# LLAP_Temp.net
KiCad netlist of a schematic drawn in EAGLE
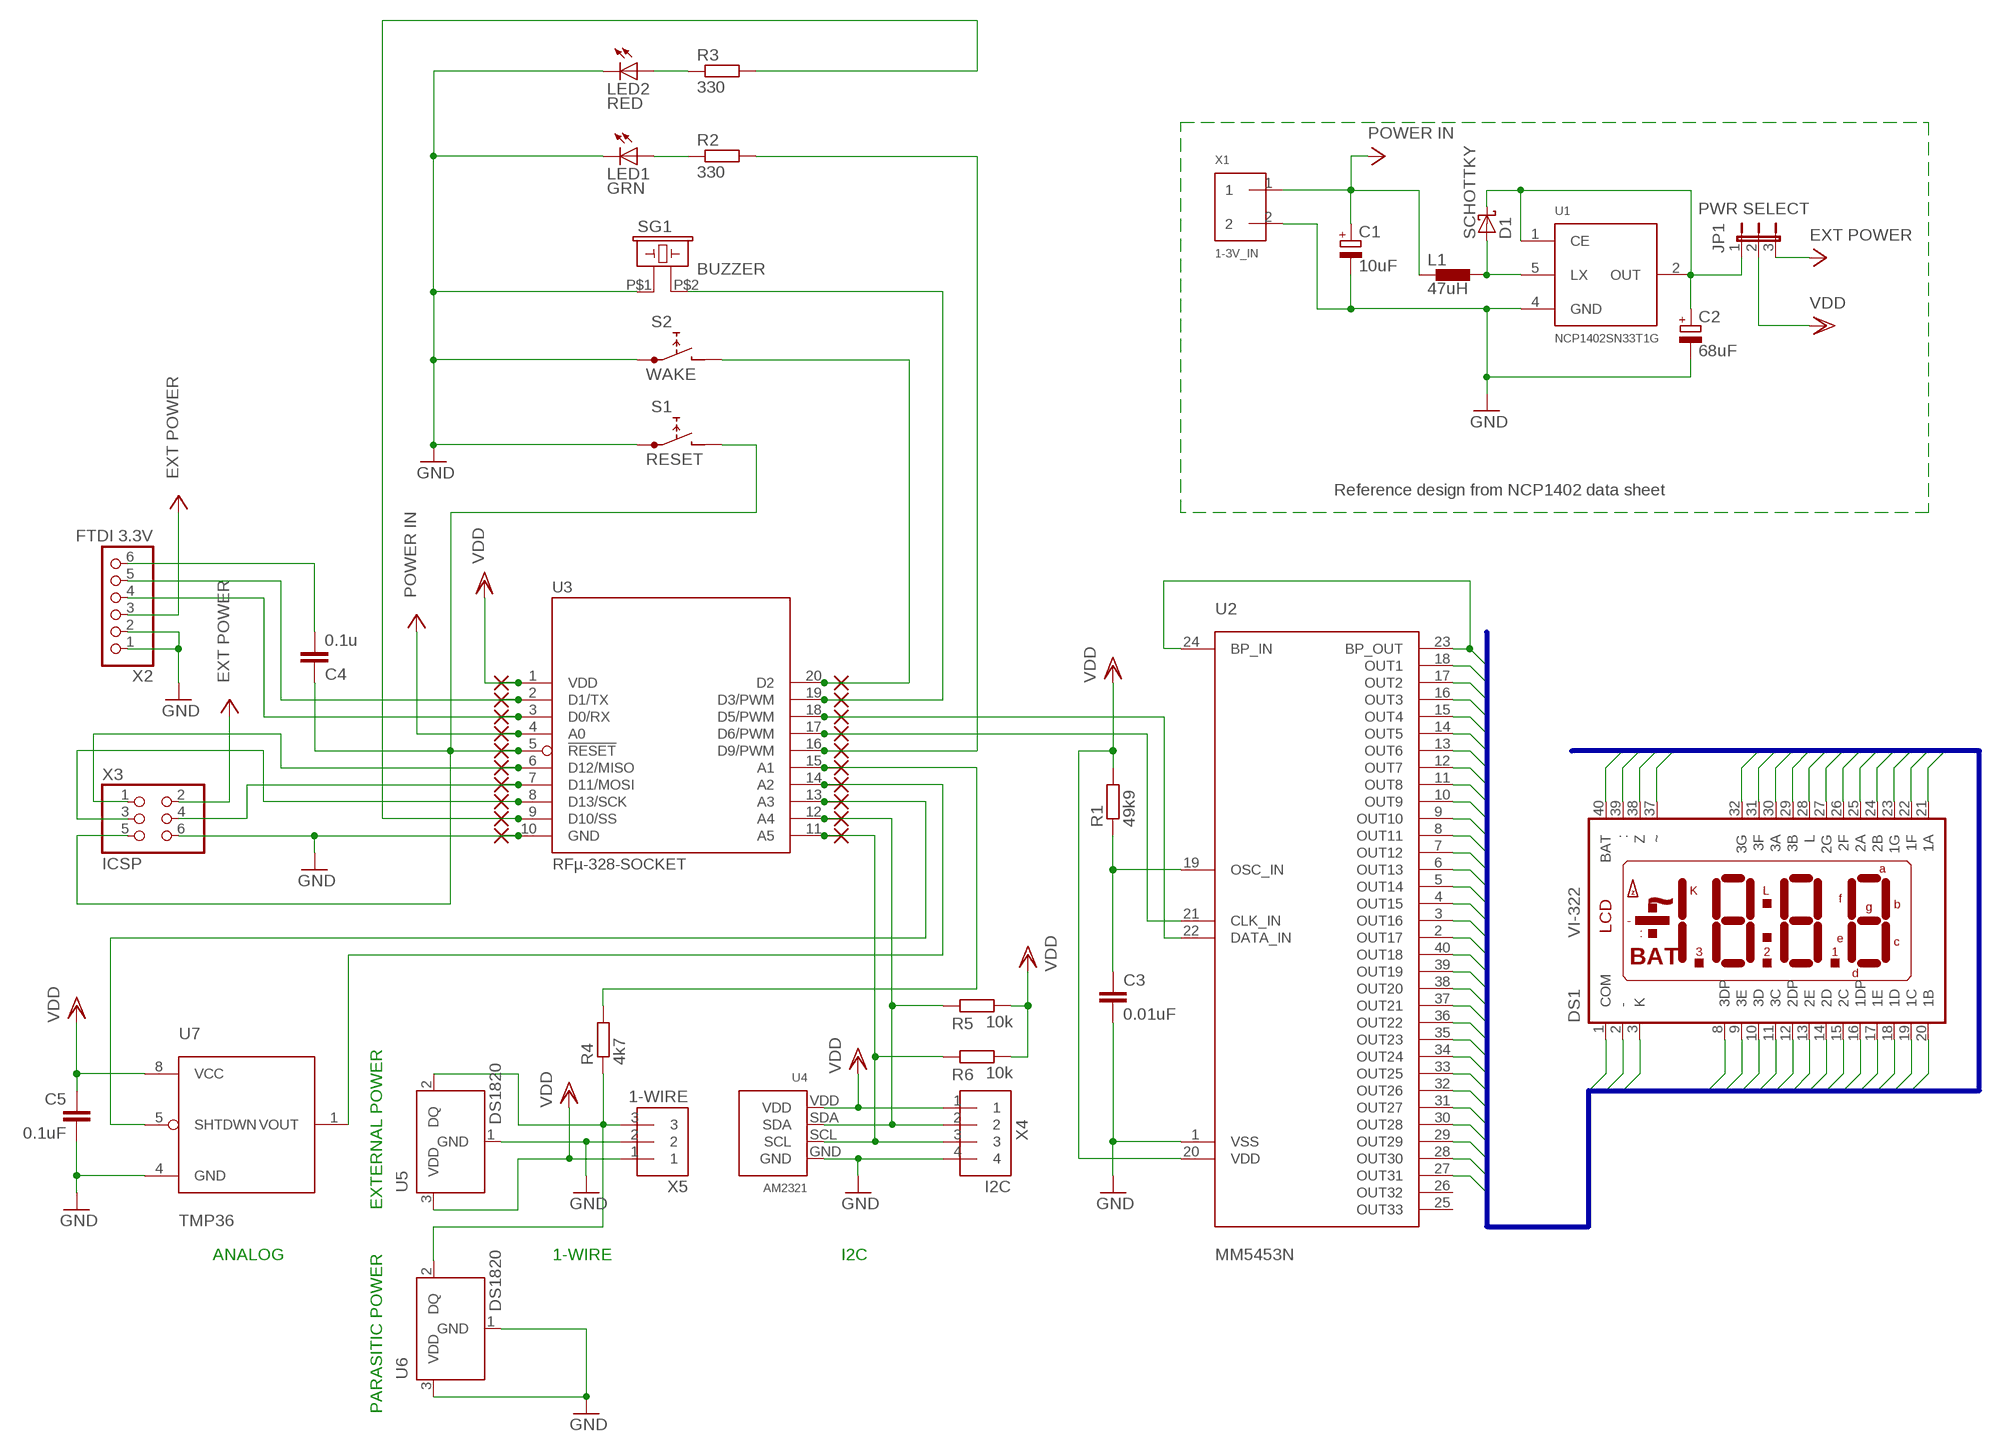
[diagram p0: schematic, sheet 1]

(export (version "E")
  (design (tool "Eeschema 10.0.6"))
  (components
    (comp (ref "C1")
      (value "10uF")
      (footprint "eagle-import:EIA6032–25")
      (libsource (lib "eagle-import") (part "T491EIA6032-25"))
    )
    (comp (ref "C2")
      (value "68uF")
      (footprint "eagle-import:EIA7343-31")
      (libsource (lib "eagle-import") (part "T491EIA7343-31"))
    )
    (comp (ref "C3")
      (value "0.01uF")
      (footprint "eagle-import:C0805")
      (libsource (lib "eagle-import") (part "C-EUC0805"))
    )
    (comp (ref "C4")
      (value "0.1u")
      (footprint "eagle-import:C0805")
      (libsource (lib "eagle-import") (part "C-EUC0805"))
    )
    (comp (ref "C5")
      (value "0.1uF")
      (footprint "eagle-import:C0805")
      (libsource (lib "eagle-import") (part "C-EUC0805"))
    )
    (comp (ref "D1")
      (value "SCHOTTKY")
      (footprint "eagle-import:SOT-123_DIODE")
      (libsource (lib "eagle-import") (part "DIODE_SCHOTTKY"))
    )
    (comp (ref "DS1")
      (value "VI-322")
      (footprint "eagle-import:LCD-VARITRONIX-VI-322")
      (libsource (lib "eagle-import") (part "LCD-VARITRONIX-VI-322"))
    )
    (comp (ref "JP1")
      (value "PWR SELECT")
      (footprint "eagle-import:JP2")
      (libsource (lib "eagle-import") (part "JP2E"))
    )
    (comp (ref "L1")
      (value "47uH")
      (footprint "eagle-import:SRN5040")
      (libsource (lib "eagle-import") (part "SRN5040SRN5040SRN5040"))
    )
    (comp (ref "LED1")
      (value "GRN")
      (footprint "eagle-import:LED3MM")
      (libsource (lib "eagle-import") (part "LED3MM"))
    )
    (comp (ref "LED2")
      (value "RED")
      (footprint "eagle-import:LED3MM")
      (libsource (lib "eagle-import") (part "LED3MM"))
    )
    (comp (ref "PAD1")
      (value "VDD")
      (footprint "eagle-import:PAD_1,6_0,9")
      (libsource (lib "eagle-import") (part "1,6/0,9"))
    )
    (comp (ref "PAD2")
      (value "TX")
      (footprint "eagle-import:PAD_1,6_0,9")
      (libsource (lib "eagle-import") (part "1,6/0,9"))
    )
    (comp (ref "PAD3")
      (value "RX")
      (footprint "eagle-import:PAD_1,6_0,9")
      (libsource (lib "eagle-import") (part "1,6/0,9"))
    )
    (comp (ref "PAD4")
      (value "BATT V.")
      (footprint "eagle-import:PAD_1,6_0,9")
      (libsource (lib "eagle-import") (part "1,6/0,9"))
    )
    (comp (ref "PAD5")
      (value "RST")
      (footprint "eagle-import:PAD_1,6_0,9")
      (libsource (lib "eagle-import") (part "1,6/0,9"))
    )
    (comp (ref "PAD6")
      (value "MISO")
      (footprint "eagle-import:PAD_1,6_0,9")
      (libsource (lib "eagle-import") (part "1,6/0,9"))
    )
    (comp (ref "PAD7")
      (value "MOSI")
      (footprint "eagle-import:PAD_1,6_0,9")
      (libsource (lib "eagle-import") (part "1,6/0,9"))
    )
    (comp (ref "PAD8")
      (value "SCK")
      (footprint "eagle-import:PAD_1,6_0,9")
      (libsource (lib "eagle-import") (part "1,6/0,9"))
    )
    (comp (ref "PAD9")
      (value "LED2")
      (footprint "eagle-import:PAD_1,6_0,9")
      (libsource (lib "eagle-import") (part "1,6/0,9"))
    )
    (comp (ref "PAD10")
      (value "GND")
      (footprint "eagle-import:PAD_1,6_0,9")
      (libsource (lib "eagle-import") (part "1,6/0,9"))
    )
    (comp (ref "PAD11")
      (value "SCL")
      (footprint "eagle-import:PAD_1,6_0,9")
      (libsource (lib "eagle-import") (part "1,6/0,9"))
    )
    (comp (ref "PAD12")
      (value "SDA")
      (footprint "eagle-import:PAD_1,6_0,9")
      (libsource (lib "eagle-import") (part "1,6/0,9"))
    )
    (comp (ref "PAD13")
      (value "TMP SHTDWN")
      (footprint "eagle-import:PAD_1,6_0,9")
      (libsource (lib "eagle-import") (part "1,6/0,9"))
    )
    (comp (ref "PAD14")
      (value "TMP MEAS.")
      (footprint "eagle-import:PAD_1,6_0,9")
      (libsource (lib "eagle-import") (part "1,6/0,9"))
    )
    (comp (ref "PAD15")
      (value "1-WIRE")
      (footprint "eagle-import:PAD_1,6_0,9")
      (libsource (lib "eagle-import") (part "1,6/0,9"))
    )
    (comp (ref "PAD16")
      (value "LED1")
      (footprint "eagle-import:PAD_1,6_0,9")
      (libsource (lib "eagle-import") (part "1,6/0,9"))
    )
    (comp (ref "PAD17")
      (value "LCD CLK")
      (footprint "eagle-import:PAD_1,6_0,9")
      (libsource (lib "eagle-import") (part "1,6/0,9"))
    )
    (comp (ref "PAD18")
      (value "LCD DATA")
      (footprint "eagle-import:PAD_1,6_0,9")
      (libsource (lib "eagle-import") (part "1,6/0,9"))
    )
    (comp (ref "PAD19")
      (value "BUZZER")
      (footprint "eagle-import:PAD_1,6_0,9")
      (libsource (lib "eagle-import") (part "1,6/0,9"))
    )
    (comp (ref "PAD20")
      (value "WAKE BTN")
      (footprint "eagle-import:PAD_1,6_0,9")
      (libsource (lib "eagle-import") (part "1,6/0,9"))
    )
    (comp (ref "R1")
      (value "49k9")
      (footprint "eagle-import:R0805")
      (libsource (lib "eagle-import") (part "R-EU_R0805"))
    )
    (comp (ref "R2")
      (value "330")
      (footprint "eagle-import:R0805")
      (libsource (lib "eagle-import") (part "R-EU_R0805"))
    )
    (comp (ref "R3")
      (value "330")
      (footprint "eagle-import:R0805")
      (libsource (lib "eagle-import") (part "R-EU_R0805"))
    )
    (comp (ref "R4")
      (value "4k7")
      (footprint "eagle-import:R0805")
      (libsource (lib "eagle-import") (part "R-EU_R0805"))
    )
    (comp (ref "R5")
      (value "10k")
      (footprint "eagle-import:R0805")
      (libsource (lib "eagle-import") (part "R-EU_R0805"))
    )
    (comp (ref "R6")
      (value "10k")
      (footprint "eagle-import:R0805")
      (libsource (lib "eagle-import") (part "R-EU_R0805"))
    )
    (comp (ref "S1")
      (value "RESET")
      (footprint "eagle-import:SWITCH-MJTP12XX")
      (libsource (lib "eagle-import") (part "SWITCH-MJTP1243/MJTP1250MJTP1243/MJTP1250"))
    )
    (comp (ref "S2")
      (value "WAKE")
      (footprint "eagle-import:SWITCH-MJTP12XX")
      (libsource (lib "eagle-import") (part "SWITCH-MJTP1243/MJTP1250MJTP1243/MJTP1250"))
    )
    (comp (ref "SG1")
      (value "BUZZER")
      (footprint "eagle-import:BUZZER-PUI_AUDIO-AT-1340-TT-R")
      (libsource (lib "eagle-import") (part "BUZZER-PUI_AUDIO-AT-1340-TT-R"))
    )
    (comp (ref "U1")
      (value "NCP1402SN33T1G")
      (footprint "eagle-import:SOT23-5L")
      (libsource (lib "eagle-import") (part "NCP1402"))
    )
    (comp (ref "U2")
      (value "MM5453N")
      (footprint "eagle-import:DIL40")
      (libsource (lib "eagle-import") (part "MM5453"))
    )
    (comp (ref "U3")
      (value "RFµ-328-SOCKET")
      (footprint "eagle-import:RFµ-328-SOCKET")
      (libsource (lib "eagle-import") (part "RFµ-328-SOCKET"))
    )
    (comp (ref "U4")
      (value "AM2321")
      (footprint "eagle-import:AM2321")
      (libsource (lib "eagle-import") (part "AOSONG-AM2321AM2321"))
    )
    (comp (ref "U5")
      (value "DS1820")
      (footprint "eagle-import:TO-92")
      (libsource (lib "eagle-import") (part "DS1820"))
    )
    (comp (ref "U6")
      (value "DS1820")
      (footprint "eagle-import:TO-92")
      (libsource (lib "eagle-import") (part "DS1820"))
    )
    (comp (ref "U7")
      (value "TMP36")
      (footprint "eagle-import:SOIC8")
      (libsource (lib "eagle-import") (part "TMP35/TMP36/TMP37SOIC8"))
    )
    (comp (ref "X1")
      (value "1-3V_IN")
      (footprint "eagle-import:CON-AMP-440055-2")
      (libsource (lib "eagle-import") (part "CON-AMP-440055-2440055-2"))
    )
    (comp (ref "X2")
      (value "FTDI 3.3V")
      (footprint "eagle-import:1X06")
      (libsource (lib "eagle-import") (part "PINHD-1X6"))
    )
    (comp (ref "X3")
      (value "ICSP")
      (footprint "eagle-import:2X03")
      (libsource (lib "eagle-import") (part "PINHD-2X3"))
    )
    (comp (ref "X4")
      (value "I2C")
      (footprint "eagle-import:CON-AMP-440055-4")
      (libsource (lib "eagle-import") (part "CON-AMP-440055-4440055-4"))
    )
    (comp (ref "X5")
      (value "1-WIRE")
      (footprint "eagle-import:CON-AMP-440055-3")
      (libsource (lib "eagle-import") (part "CON-AMP-440055-3440055-3"))
    )
  )
  (nets
    (net (code "1") (name "/BP") (class "Default")
      (node (ref "DS1") (pin "1") (pinfunction "COM_1") (pintype "passive"))
      (node (ref "U2") (pin "23") (pinfunction "BP_OUT_23") (pintype "output"))
      (node (ref "U2") (pin "24") (pinfunction "BP_IN_24") (pintype "input"))
    )
    (net (code "2") (name "/LCD1") (class "Default")
      (node (ref "DS1") (pin "21") (pinfunction "1A_21") (pintype "passive"))
      (node (ref "U2") (pin "18") (pinfunction "OUT1_18") (pintype "output"))
    )
    (net (code "3") (name "/LCD2") (class "Default")
      (node (ref "DS1") (pin "20") (pinfunction "1B_20") (pintype "passive"))
      (node (ref "U2") (pin "17") (pinfunction "OUT2_17") (pintype "output"))
    )
    (net (code "4") (name "/LCD3") (class "Default")
      (node (ref "DS1") (pin "19") (pinfunction "1C_19") (pintype "passive"))
      (node (ref "U2") (pin "16") (pinfunction "OUT3_16") (pintype "output"))
    )
    (net (code "5") (name "/LCD4") (class "Default")
      (node (ref "DS1") (pin "18") (pinfunction "1D_18") (pintype "passive"))
      (node (ref "U2") (pin "15") (pinfunction "OUT4_15") (pintype "output"))
    )
    (net (code "6") (name "/LCD5") (class "Default")
      (node (ref "DS1") (pin "17") (pinfunction "1E_17") (pintype "passive"))
      (node (ref "U2") (pin "14") (pinfunction "OUT5_14") (pintype "output"))
    )
    (net (code "7") (name "/LCD6") (class "Default")
      (node (ref "DS1") (pin "22") (pinfunction "1F_22") (pintype "passive"))
      (node (ref "U2") (pin "13") (pinfunction "OUT6_13") (pintype "output"))
    )
    (net (code "8") (name "/LCD7") (class "Default")
      (node (ref "DS1") (pin "23") (pinfunction "1G_23") (pintype "passive"))
      (node (ref "U2") (pin "12") (pinfunction "OUT7_12") (pintype "output"))
    )
    (net (code "9") (name "/LCD8") (class "Default")
      (node (ref "DS1") (pin "16") (pinfunction "1DP_16") (pintype "passive"))
      (node (ref "U2") (pin "11") (pinfunction "OUT8_11") (pintype "output"))
    )
    (net (code "10") (name "/LCD9") (class "Default")
      (node (ref "DS1") (pin "25") (pinfunction "2A_25") (pintype "passive"))
      (node (ref "U2") (pin "10") (pinfunction "OUT9_10") (pintype "output"))
    )
    (net (code "11") (name "/LCD10") (class "Default")
      (node (ref "DS1") (pin "24") (pinfunction "2B_24") (pintype "passive"))
      (node (ref "U2") (pin "9") (pinfunction "OUT10_9") (pintype "output"))
    )
    (net (code "12") (name "/LCD11") (class "Default")
      (node (ref "DS1") (pin "15") (pinfunction "2C_15") (pintype "passive"))
      (node (ref "U2") (pin "8") (pinfunction "OUT11_8") (pintype "output"))
    )
    (net (code "13") (name "/LCD12") (class "Default")
      (node (ref "DS1") (pin "14") (pinfunction "2D_14") (pintype "passive"))
      (node (ref "U2") (pin "7") (pinfunction "OUT12_7") (pintype "output"))
    )
    (net (code "14") (name "/LCD13") (class "Default")
      (node (ref "DS1") (pin "13") (pinfunction "2E_13") (pintype "passive"))
      (node (ref "U2") (pin "6") (pinfunction "OUT13_6") (pintype "output"))
    )
    (net (code "15") (name "/LCD14") (class "Default")
      (node (ref "DS1") (pin "26") (pinfunction "2F_26") (pintype "passive"))
      (node (ref "U2") (pin "5") (pinfunction "OUT14_5") (pintype "output"))
    )
    (net (code "16") (name "/LCD15") (class "Default")
      (node (ref "DS1") (pin "27") (pinfunction "2G_27") (pintype "passive"))
      (node (ref "U2") (pin "4") (pinfunction "OUT15_4") (pintype "output"))
    )
    (net (code "17") (name "/LCD16") (class "Default")
      (node (ref "DS1") (pin "12") (pinfunction "2DP_12") (pintype "passive"))
      (node (ref "U2") (pin "3") (pinfunction "OUT16_3") (pintype "output"))
    )
    (net (code "18") (name "/LCD17") (class "Default")
      (node (ref "DS1") (pin "28") (pinfunction "L_28") (pintype "passive"))
      (node (ref "U2") (pin "2") (pinfunction "OUT17_2") (pintype "output"))
    )
    (net (code "19") (name "/LCD18") (class "Default")
      (node (ref "DS1") (pin "30") (pinfunction "3A_30") (pintype "passive"))
      (node (ref "U2") (pin "40") (pinfunction "OUT18_40") (pintype "output"))
    )
    (net (code "20") (name "/LCD19") (class "Default")
      (node (ref "DS1") (pin "29") (pinfunction "3B_29") (pintype "passive"))
      (node (ref "U2") (pin "39") (pinfunction "OUT19_39") (pintype "output"))
    )
    (net (code "21") (name "/LCD20") (class "Default")
      (node (ref "DS1") (pin "11") (pinfunction "3C_11") (pintype "passive"))
      (node (ref "U2") (pin "38") (pinfunction "OUT20_38") (pintype "output"))
    )
    (net (code "22") (name "/LCD21") (class "Default")
      (node (ref "DS1") (pin "10") (pinfunction "3D_10") (pintype "passive"))
      (node (ref "U2") (pin "37") (pinfunction "OUT21_37") (pintype "output"))
    )
    (net (code "23") (name "/LCD22") (class "Default")
      (node (ref "DS1") (pin "9") (pinfunction "3E_9") (pintype "passive"))
      (node (ref "U2") (pin "36") (pinfunction "OUT22_36") (pintype "output"))
    )
    (net (code "24") (name "/LCD23") (class "Default")
      (node (ref "DS1") (pin "31") (pinfunction "3F_31") (pintype "passive"))
      (node (ref "U2") (pin "35") (pinfunction "OUT23_35") (pintype "output"))
    )
    (net (code "25") (name "/LCD24") (class "Default")
      (node (ref "DS1") (pin "32") (pinfunction "3G_32") (pintype "passive"))
      (node (ref "U2") (pin "34") (pinfunction "OUT24_34") (pintype "output"))
    )
    (net (code "26") (name "/LCD25") (class "Default")
      (node (ref "DS1") (pin "8") (pinfunction "3DP_8") (pintype "passive"))
      (node (ref "U2") (pin "33") (pinfunction "OUT25_33") (pintype "output"))
    )
    (net (code "27") (name "/LCD26") (class "Default")
      (node (ref "DS1") (pin "3") (pinfunction "K_3") (pintype "passive"))
      (node (ref "U2") (pin "32") (pinfunction "OUT26_32") (pintype "output"))
    )
    (net (code "28") (name "/LCD27") (class "Default")
      (node (ref "DS1") (pin "2") (pinfunction "-_2") (pintype "passive"))
      (node (ref "U2") (pin "31") (pinfunction "OUT27_31") (pintype "output"))
    )
    (net (code "29") (name "/LCD28") (class "Default")
      (node (ref "DS1") (pin "39") (pinfunction ":_39") (pintype "passive"))
      (node (ref "U2") (pin "30") (pinfunction "OUT28_30") (pintype "output"))
    )
    (net (code "30") (name "/LCD29") (class "Default")
      (node (ref "DS1") (pin "40") (pinfunction "BAT_40") (pintype "passive"))
      (node (ref "U2") (pin "29") (pinfunction "OUT29_29") (pintype "output"))
    )
    (net (code "31") (name "/LCD30") (class "Default")
      (node (ref "DS1") (pin "38") (pinfunction "Z_38") (pintype "passive"))
      (node (ref "U2") (pin "28") (pinfunction "OUT30_28") (pintype "output"))
    )
    (net (code "32") (name "/LCD31") (class "Default")
      (node (ref "DS1") (pin "37") (pinfunction "~_37") (pintype "passive"))
      (node (ref "U2") (pin "27") (pinfunction "OUT31_27") (pintype "output"))
    )
    (net (code "33") (name "EXT POWER") (class "Default")
      (node (ref "JP1") (pin "3") (pinfunction "3_3") (pintype "passive"))
      (node (ref "X2") (pin "3") (pinfunction "3_3") (pintype "passive"))
      (node (ref "X3") (pin "2") (pinfunction "2_2") (pintype "passive"))
    )
    (net (code "34") (name "GND") (class "Default")
      (node (ref "C1") (pin "P$1") (pinfunction "-_P$1") (pintype "passive"))
      (node (ref "C2") (pin "P$1") (pinfunction "-_P$1") (pintype "passive"))
      (node (ref "C3") (pin "2") (pinfunction "2_2") (pintype "passive"))
      (node (ref "C5") (pin "2") (pinfunction "2_2") (pintype "passive"))
      (node (ref "LED1") (pin "K") (pinfunction "C_K") (pintype "passive"))
      (node (ref "LED2") (pin "K") (pinfunction "C_K") (pintype "passive"))
      (node (ref "PAD10") (pin "1") (pinfunction "P_1") (pintype "passive"))
      (node (ref "S1") (pin "P$1") (pinfunction "1_P$1") (pintype "passive"))
      (node (ref "S2") (pin "P$1") (pinfunction "1_P$1") (pintype "passive"))
      (node (ref "SG1") (pin "P$1") (pinfunction "1_P$1") (pintype "passive"))
      (node (ref "U1") (pin "4") (pinfunction "GND_4") (pintype "power_in"))
      (node (ref "U2") (pin "1") (pinfunction "VSS_1") (pintype "power_in"))
      (node (ref "U3") (pin "10") (pinfunction "GND_10") (pintype "power_in"))
      (node (ref "U4") (pin "GND") (pinfunction "GND_GND") (pintype "power_in"))
      (node (ref "U5") (pin "1") (pinfunction "GND_1") (pintype "power_in"))
      (node (ref "U6") (pin "1") (pinfunction "GND_1") (pintype "power_in"))
      (node (ref "U6") (pin "3") (pinfunction "VDD_3") (pintype "input"))
      (node (ref "U7") (pin "4") (pinfunction "GND_4") (pintype "power_in"))
      (node (ref "X1") (pin "2") (pinfunction "2_2") (pintype "passive"))
      (node (ref "X2") (pin "1") (pinfunction "1_1") (pintype "passive"))
      (node (ref "X2") (pin "2") (pinfunction "2_2") (pintype "passive"))
      (node (ref "X3") (pin "6") (pinfunction "6_6") (pintype "passive"))
      (node (ref "X4") (pin "4") (pinfunction "4_4") (pintype "passive"))
      (node (ref "X5") (pin "2") (pinfunction "2_2") (pintype "passive"))
    )
    (net (code "35") (name "Net-(C2-+)") (class "Default")
      (node (ref "C2") (pin "P$2") (pinfunction "+_P$2") (pintype "passive"))
      (node (ref "D1") (pin "C") (pinfunction "C_C") (pintype "passive"))
      (node (ref "JP1") (pin "1") (pinfunction "1_1") (pintype "passive"))
      (node (ref "U1") (pin "1") (pinfunction "CE_1") (pintype "input"))
      (node (ref "U1") (pin "2") (pinfunction "OUT_2") (pintype "power_in"))
    )
    (net (code "36") (name "Net-(C4-Pad2)") (class "Default")
      (node (ref "C4") (pin "2") (pinfunction "2_2") (pintype "passive"))
      (node (ref "X2") (pin "6") (pinfunction "6_6") (pintype "passive"))
    )
    (net (code "37") (name "Net-(LED1-PadA)") (class "Default")
      (node (ref "LED1") (pin "A") (pinfunction "A_A") (pintype "passive"))
      (node (ref "R2") (pin "1") (pinfunction "1_1") (pintype "passive"))
    )
    (net (code "38") (name "Net-(LED2-PadA)") (class "Default")
      (node (ref "LED2") (pin "A") (pinfunction "A_A") (pintype "passive"))
      (node (ref "R3") (pin "1") (pinfunction "1_1") (pintype "passive"))
    )
    (net (code "39") (name "Net-(PAD2-P)") (class "Default")
      (node (ref "PAD2") (pin "1") (pinfunction "P_1") (pintype "passive"))
      (node (ref "U3") (pin "2") (pinfunction "D1/TX_2") (pintype "output"))
      (node (ref "X2") (pin "5") (pinfunction "5_5") (pintype "passive"))
    )
    (net (code "40") (name "Net-(PAD3-P)") (class "Default")
      (node (ref "PAD3") (pin "1") (pinfunction "P_1") (pintype "passive"))
      (node (ref "U3") (pin "3") (pinfunction "D0/RX_3") (pintype "input"))
      (node (ref "X2") (pin "4") (pinfunction "4_4") (pintype "passive"))
    )
    (net (code "41") (name "Net-(PAD5-P)") (class "Default")
      (node (ref "C4") (pin "1") (pinfunction "1_1") (pintype "passive"))
      (node (ref "PAD5") (pin "1") (pinfunction "P_1") (pintype "passive"))
      (node (ref "S1") (pin "P$2") (pinfunction "2_P$2") (pintype "passive"))
      (node (ref "U3") (pin "5") (pinfunction "~{RESET}_5") (pintype "input"))
      (node (ref "X3") (pin "5") (pinfunction "5_5") (pintype "passive"))
    )
    (net (code "42") (name "Net-(PAD6-P)") (class "Default")
      (node (ref "PAD6") (pin "1") (pinfunction "P_1") (pintype "passive"))
      (node (ref "U3") (pin "6") (pinfunction "D12/MISO_6") (pintype "bidirectional"))
      (node (ref "X3") (pin "1") (pinfunction "1_1") (pintype "passive"))
    )
    (net (code "43") (name "Net-(PAD7-P)") (class "Default")
      (node (ref "PAD7") (pin "1") (pinfunction "P_1") (pintype "passive"))
      (node (ref "U3") (pin "7") (pinfunction "D11/MOSI_7") (pintype "bidirectional"))
      (node (ref "X3") (pin "4") (pinfunction "4_4") (pintype "passive"))
    )
    (net (code "44") (name "Net-(PAD8-P)") (class "Default")
      (node (ref "PAD8") (pin "1") (pinfunction "P_1") (pintype "passive"))
      (node (ref "U3") (pin "8") (pinfunction "D13/SCK_8") (pintype "bidirectional"))
      (node (ref "X3") (pin "3") (pinfunction "3_3") (pintype "passive"))
    )
    (net (code "45") (name "Net-(PAD9-P)") (class "Default")
      (node (ref "PAD9") (pin "1") (pinfunction "P_1") (pintype "passive"))
      (node (ref "R3") (pin "2") (pinfunction "2_2") (pintype "passive"))
      (node (ref "U3") (pin "9") (pinfunction "D10/SS_9") (pintype "bidirectional"))
    )
    (net (code "46") (name "Net-(PAD11-P)") (class "Default")
      (node (ref "PAD11") (pin "1") (pinfunction "P_1") (pintype "passive"))
      (node (ref "R6") (pin "1") (pinfunction "1_1") (pintype "passive"))
      (node (ref "U3") (pin "11") (pinfunction "A5_11") (pintype "bidirectional"))
      (node (ref "U4") (pin "SCL") (pinfunction "SCL_SCL") (pintype "bidirectional"))
      (node (ref "X4") (pin "3") (pinfunction "3_3") (pintype "passive"))
    )
    (net (code "47") (name "Net-(PAD12-P)") (class "Default")
      (node (ref "PAD12") (pin "1") (pinfunction "P_1") (pintype "passive"))
      (node (ref "R5") (pin "1") (pinfunction "1_1") (pintype "passive"))
      (node (ref "U3") (pin "12") (pinfunction "A4_12") (pintype "output"))
      (node (ref "U4") (pin "SDA") (pinfunction "SDA_SDA") (pintype "bidirectional"))
      (node (ref "X4") (pin "2") (pinfunction "2_2") (pintype "passive"))
    )
    (net (code "48") (name "Net-(PAD13-P)") (class "Default")
      (node (ref "PAD13") (pin "1") (pinfunction "P_1") (pintype "passive"))
      (node (ref "U3") (pin "13") (pinfunction "A3_13") (pintype "bidirectional"))
      (node (ref "U7") (pin "5") (pinfunction "SHTDWN_5") (pintype "input"))
    )
    (net (code "49") (name "Net-(PAD14-P)") (class "Default")
      (node (ref "PAD14") (pin "1") (pinfunction "P_1") (pintype "passive"))
      (node (ref "U3") (pin "14") (pinfunction "A2_14") (pintype "bidirectional"))
      (node (ref "U7") (pin "1") (pinfunction "VOUT_1") (pintype "output"))
    )
    (net (code "50") (name "Net-(PAD15-P)") (class "Default")
      (node (ref "PAD15") (pin "1") (pinfunction "P_1") (pintype "passive"))
      (node (ref "R4") (pin "2") (pinfunction "2_2") (pintype "passive"))
      (node (ref "U3") (pin "15") (pinfunction "A1_15") (pintype "bidirectional"))
    )
    (net (code "51") (name "Net-(PAD16-P)") (class "Default")
      (node (ref "PAD16") (pin "1") (pinfunction "P_1") (pintype "passive"))
      (node (ref "R2") (pin "2") (pinfunction "2_2") (pintype "passive"))
      (node (ref "U3") (pin "16") (pinfunction "D9/PWM_16") (pintype "input"))
    )
    (net (code "52") (name "Net-(PAD17-P)") (class "Default")
      (node (ref "PAD17") (pin "1") (pinfunction "P_1") (pintype "passive"))
      (node (ref "U2") (pin "21") (pinfunction "CLK_IN_21") (pintype "input"))
      (node (ref "U3") (pin "17") (pinfunction "D6/PWM_17") (pintype "bidirectional"))
    )
    (net (code "53") (name "Net-(PAD18-P)") (class "Default")
      (node (ref "PAD18") (pin "1") (pinfunction "P_1") (pintype "passive"))
      (node (ref "U2") (pin "22") (pinfunction "DATA_IN_22") (pintype "input"))
      (node (ref "U3") (pin "18") (pinfunction "D5/PWM_18") (pintype "bidirectional"))
    )
    (net (code "54") (name "Net-(PAD19-P)") (class "Default")
      (node (ref "PAD19") (pin "1") (pinfunction "P_1") (pintype "passive"))
      (node (ref "SG1") (pin "P$2") (pinfunction "2_P$2") (pintype "passive"))
      (node (ref "U3") (pin "19") (pinfunction "D3/PWM_19") (pintype "bidirectional"))
    )
    (net (code "55") (name "Net-(PAD20-P)") (class "Default")
      (node (ref "PAD20") (pin "1") (pinfunction "P_1") (pintype "passive"))
      (node (ref "S2") (pin "P$2") (pinfunction "2_P$2") (pintype "passive"))
      (node (ref "U3") (pin "20") (pinfunction "D2_20") (pintype "bidirectional"))
    )
    (net (code "56") (name "Net-(U1-LX)") (class "Default")
      (node (ref "D1") (pin "A") (pinfunction "A_A") (pintype "passive"))
      (node (ref "L1") (pin "2") (pinfunction "2_2") (pintype "passive"))
      (node (ref "U1") (pin "5") (pinfunction "LX_5") (pintype "input"))
    )
    (net (code "57") (name "Net-(U2-OSC_IN)") (class "Default")
      (node (ref "C3") (pin "1") (pinfunction "1_1") (pintype "passive"))
      (node (ref "R1") (pin "1") (pinfunction "1_1") (pintype "passive"))
      (node (ref "U2") (pin "19") (pinfunction "OSC_IN_19") (pintype "input"))
    )
    (net (code "58") (name "Net-(U5-DQ)") (class "Default")
      (node (ref "R4") (pin "1") (pinfunction "1_1") (pintype "passive"))
      (node (ref "U5") (pin "2") (pinfunction "DQ_2") (pintype "output"))
      (node (ref "U6") (pin "2") (pinfunction "DQ_2") (pintype "output"))
      (node (ref "X5") (pin "3") (pinfunction "3_3") (pintype "passive"))
    )
    (net (code "59") (name "POWER IN") (class "Default")
      (node (ref "C1") (pin "P$2") (pinfunction "+_P$2") (pintype "passive"))
      (node (ref "L1") (pin "1") (pinfunction "1_1") (pintype "passive"))
      (node (ref "PAD4") (pin "1") (pinfunction "P_1") (pintype "passive"))
      (node (ref "U3") (pin "4") (pinfunction "A0_4") (pintype "bidirectional"))
      (node (ref "X1") (pin "1") (pinfunction "1_1") (pintype "passive"))
    )
    (net (code "60") (name "VDD") (class "Default")
      (node (ref "C5") (pin "1") (pinfunction "1_1") (pintype "passive"))
      (node (ref "JP1") (pin "2") (pinfunction "2_2") (pintype "passive"))
      (node (ref "PAD1") (pin "1") (pinfunction "P_1") (pintype "passive"))
      (node (ref "R1") (pin "2") (pinfunction "2_2") (pintype "passive"))
      (node (ref "R5") (pin "2") (pinfunction "2_2") (pintype "passive"))
      (node (ref "R6") (pin "2") (pinfunction "2_2") (pintype "passive"))
      (node (ref "U2") (pin "20") (pinfunction "VDD_20") (pintype "power_in"))
      (node (ref "U3") (pin "1") (pinfunction "VDD_1") (pintype "power_in"))
      (node (ref "U4") (pin "VDD") (pinfunction "VDD_VDD") (pintype "power_in"))
      (node (ref "U5") (pin "3") (pinfunction "VDD_3") (pintype "input"))
      (node (ref "U7") (pin "8") (pinfunction "VCC_8") (pintype "power_in"))
      (node (ref "X4") (pin "1") (pinfunction "1_1") (pintype "passive"))
      (node (ref "X5") (pin "1") (pinfunction "1_1") (pintype "passive"))
    )
    (net (code "61") (name "unconnected-(U2-OUT32-Pad26)") (class "Default")
      (node (ref "U2") (pin "26") (pinfunction "OUT32_26") (pintype "output"))
    )
    (net (code "62") (name "unconnected-(U2-OUT33-Pad25)") (class "Default")
      (node (ref "U2") (pin "25") (pinfunction "OUT33_25") (pintype "output"))
    )
  )
)
